# Power_Supply.net
KiCad netlist of a schematic drawn in Altium Designer
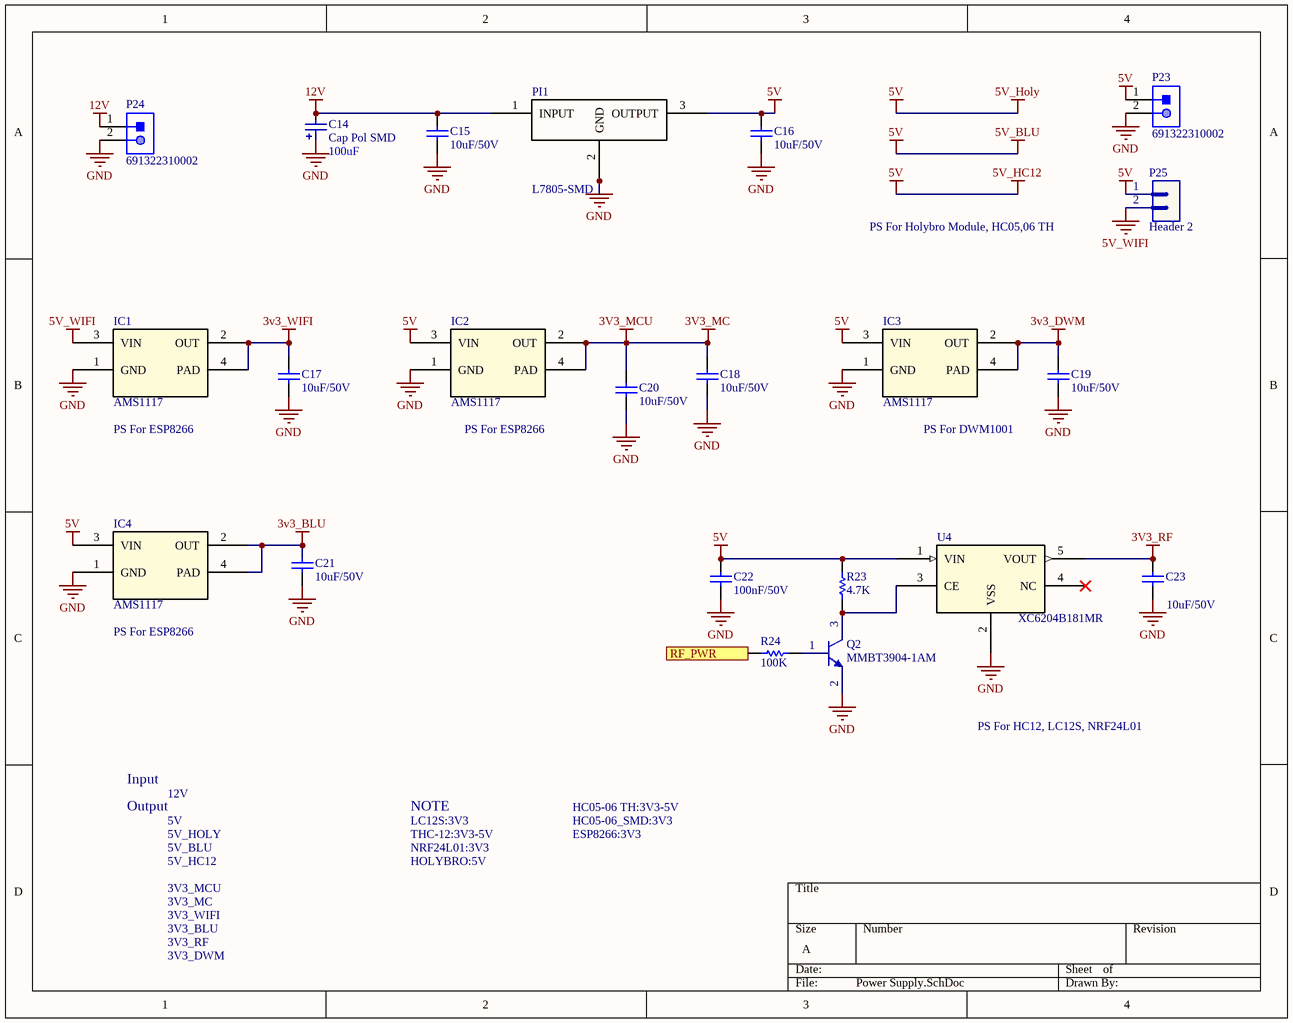
[diagram p0: Power Supply.SchDoc]

(export (version "E")
  (design (tool "Eeschema 10.0.6"))
  (components
    (comp (ref "C14")
      (value "Cap Pol SMD")
      (footprint "CAP ALU SIZE B")
      (description "Polarized Capacitor (Radial)")
      (fields (field (name "ALTIUM_VALUE") "100uF"))
      (libsource (lib "PIF_C16_lib") (part "Cap Pol SMD"))
    )
    (comp (ref "C15")
      (value "10uF/50V")
      (footprint "CAP-SM-0805")
      (description "CAP CER 10UF 50V X5R 0805")
      (fields
        (field (name "MANUFACTURER") "Yageo")
        (field (name "MANUFACTURER PART NUMBER") "CC0805KKX5R9BB106")
      )
      (libsource (lib "Capacitor") (part "Cap-10uF-50V-0805"))
    )
    (comp (ref "C16")
      (value "10uF/50V")
      (footprint "CAP-SM-0805")
      (description "CAP CER 10UF 50V X5R 0805")
      (fields
        (field (name "MANUFACTURER") "Yageo")
        (field (name "MANUFACTURER PART NUMBER") "CC0805KKX5R9BB106")
      )
      (libsource (lib "Capacitor") (part "Cap-10uF-50V-0805"))
    )
    (comp (ref "C17")
      (value "10uF/50V")
      (footprint "CAP-SM-0805")
      (description "CAP CER 10UF 50V X5R 0805")
      (fields
        (field (name "MANUFACTURER") "Yageo")
        (field (name "MANUFACTURER PART NUMBER") "CC0805KKX5R9BB106")
      )
      (libsource (lib "Capacitor") (part "Cap-10uF-50V-0805"))
    )
    (comp (ref "C18")
      (value "10uF/50V")
      (footprint "CAP-SM-0805")
      (description "CAP CER 10UF 50V X5R 0805")
      (fields
        (field (name "MANUFACTURER") "Yageo")
        (field (name "MANUFACTURER PART NUMBER") "CC0805KKX5R9BB106")
      )
      (libsource (lib "Capacitor") (part "Cap-10uF-50V-0805"))
    )
    (comp (ref "C19")
      (value "10uF/50V")
      (footprint "CAP-SM-0805")
      (description "CAP CER 10UF 50V X5R 0805")
      (fields
        (field (name "MANUFACTURER") "Yageo")
        (field (name "MANUFACTURER PART NUMBER") "CC0805KKX5R9BB106")
      )
      (libsource (lib "Capacitor") (part "Cap-10uF-50V-0805"))
    )
    (comp (ref "C20")
      (value "10uF/50V")
      (footprint "CAP-SM-0805")
      (description "CAP CER 10UF 50V X5R 0805")
      (fields
        (field (name "MANUFACTURER") "Yageo")
        (field (name "MANUFACTURER PART NUMBER") "CC0805KKX5R9BB106")
      )
      (libsource (lib "Capacitor") (part "Cap-10uF-50V-0805"))
    )
    (comp (ref "C21")
      (value "10uF/50V")
      (footprint "CAP-SM-0805")
      (description "CAP CER 10UF 50V X5R 0805")
      (fields
        (field (name "MANUFACTURER") "Yageo")
        (field (name "MANUFACTURER PART NUMBER") "CC0805KKX5R9BB106")
      )
      (libsource (lib "Capacitor") (part "Cap-10uF-50V-0805"))
    )
    (comp (ref "C22")
      (value "100nF/50V")
      (footprint "CAP-SM-0805")
      (description "CAP CER 0.1UF 50V Y5V 0805")
      (fields
        (field (name "MANUFACTURER") "Samsung Electro-Mechanics")
        (field (name "MANUFACTURER PART NUMBER") "CL21F104ZBCNNNC")
      )
      (libsource (lib "Capacitor") (part "Cap-100nF-50V-0805"))
    )
    (comp (ref "C23")
      (value "10uF/50V")
      (footprint "CAP-SM-0805")
      (description "CAP CER 10UF 50V X5R 0805")
      (fields
        (field (name "MANUFACTURER") "Yageo")
        (field (name "MANUFACTURER PART NUMBER") "CC0805KKX5R9BB106")
      )
      (libsource (lib "Capacitor") (part "Cap-10uF-50V-0805"))
    )
    (comp (ref "IC1")
      (value "AMS1117")
      (footprint "AMS1117")
      (fields (field (name "COPYRIGHT") "Copyright (C) 2018 Accelerated Designs. All rights reserved"))
      (libsource (lib "Integrated_Library") (part "AMS1117"))
    )
    (comp (ref "IC2")
      (value "AMS1117")
      (footprint "AMS1117")
      (fields (field (name "COPYRIGHT") "Copyright (C) 2018 Accelerated Designs. All rights reserved"))
      (libsource (lib "Integrated_Library") (part "AMS1117"))
    )
    (comp (ref "IC3")
      (value "AMS1117")
      (footprint "AMS1117")
      (fields (field (name "COPYRIGHT") "Copyright (C) 2018 Accelerated Designs. All rights reserved"))
      (libsource (lib "Integrated_Library") (part "AMS1117"))
    )
    (comp (ref "IC4")
      (value "AMS1117")
      (footprint "AMS1117")
      (fields (field (name "COPYRIGHT") "Copyright (C) 2018 Accelerated Designs. All rights reserved"))
      (libsource (lib "Integrated_Library") (part "AMS1117"))
    )
    (comp (ref "P23")
      (value "691322310002")
      (footprint "691322310002")
      (description "WR-TBL Serie 322 Horizontal PCB Header, Pluggable, pitch 3.81mm, 2p")
      (fields (field (name "PUBLISHER") "Wurth Elektronik"))
      (libsource (lib "691101710002_Altium_WR-TBL_rev19a") (part "691322310002"))
    )
    (comp (ref "P24")
      (value "691322310002")
      (footprint "691322310002")
      (description "WR-TBL Serie 322 Horizontal PCB Header, Pluggable, pitch 3.81mm, 2p")
      (fields (field (name "PUBLISHER") "Wurth Elektronik"))
      (libsource (lib "691101710002_Altium_WR-TBL_rev19a") (part "691322310002"))
    )
    (comp (ref "P25")
      (value "Header 2")
      (footprint "JP2")
      (description "Header, 2-Pin")
      (fields (field (name "PUBLISHER") "Altium Limited"))
      (libsource (lib "PIF_C16_lib") (part "Header 2"))
    )
    (comp (ref "PI1")
      (value "L7805-SMD")
      (footprint "D2PAk")
      (fields
        (field (name "MANUFACTURER_PART_NUMBER") "L7805CD2T-TR")
        (field (name "COPYRIGHT") "Copyright (C) 2018 Accelerated Designs. All rights reserved")
      )
      (libsource (lib "Integrated_Library") (part "L7805-SMD_1"))
    )
    (comp (ref "Q2")
      (value "MMBT3904-1AM")
      (footprint "SOT23_NEX")
      (libsource (lib "BJT") (part "MMBT3904-1AM"))
    )
    (comp (ref "R23")
      (value "4.7K")
      (footprint "Resistor:RES-SM-0805")
      (description "RES 1K OHM 1% 1/4W 0805")
      (fields
        (field (name "MANUFACTURER") "Stackpole Electronics Inc")
        (field (name "MANUFACTURER PART NUMBER") "RNCP0805FTD1K00")
      )
      (libsource (lib "Resistor") (part "Res-1K-0805"))
    )
    (comp (ref "R24")
      (value "100K")
      (footprint "Resistor:RES-SM-0805")
      (description "RES 1K OHM 1% 1/4W 0805")
      (fields
        (field (name "MANUFACTURER") "Stackpole Electronics Inc")
        (field (name "MANUFACTURER PART NUMBER") "RNCP0805FTD1K00")
      )
      (libsource (lib "Resistor") (part "Res-1K-0805"))
    )
    (comp (ref "U4")
      (value "XC6204B181MR")
      (footprint "XC6204B332MR")
      (fields (field (name "COPYRIGHT") "Copyright (C) 2018 Accelerated Designs. All rights reserved"))
      (libsource (lib "Integrated_Library") (part "XC6204B181MR"))
    )
  )
  (nets
    (net (code "1") (name "/RF_PWR") (class "Default")
      (node (ref "R24") (pin "2") (pinfunction "2_2") (pintype "passive"))
    )
    (net (code "2") (name "3V3_MC") (class "Default")
      (node (ref "C18") (pin "2") (pinfunction "2_2") (pintype "passive"))
      (node (ref "C20") (pin "2") (pinfunction "2_2") (pintype "passive"))
      (node (ref "IC2") (pin "2") (pinfunction "OUT_2") (pintype "open_collector"))
      (node (ref "IC2") (pin "4") (pinfunction "PAD_4") (pintype "power_in"))
    )
    (net (code "3") (name "3V3_RF") (class "Default")
      (node (ref "C23") (pin "2") (pinfunction "2_2") (pintype "passive"))
      (node (ref "U4") (pin "5") (pinfunction "VOUT_5") (pintype "output"))
    )
    (net (code "4") (name "3v3_BLU") (class "Default")
      (node (ref "C21") (pin "2") (pinfunction "2_2") (pintype "passive"))
      (node (ref "IC4") (pin "2") (pinfunction "OUT_2") (pintype "open_collector"))
      (node (ref "IC4") (pin "4") (pinfunction "PAD_4") (pintype "power_in"))
    )
    (net (code "5") (name "3v3_DWM") (class "Default")
      (node (ref "C19") (pin "2") (pinfunction "2_2") (pintype "passive"))
      (node (ref "IC3") (pin "2") (pinfunction "OUT_2") (pintype "open_collector"))
      (node (ref "IC3") (pin "4") (pinfunction "PAD_4") (pintype "power_in"))
    )
    (net (code "6") (name "3v3_WIFI") (class "Default")
      (node (ref "C17") (pin "2") (pinfunction "2_2") (pintype "passive"))
      (node (ref "IC1") (pin "2") (pinfunction "OUT_2") (pintype "open_collector"))
      (node (ref "IC1") (pin "4") (pinfunction "PAD_4") (pintype "power_in"))
    )
    (net (code "7") (name "5V") (class "Default")
      (node (ref "C16") (pin "2") (pinfunction "2_2") (pintype "passive"))
      (node (ref "C22") (pin "2") (pinfunction "2_2") (pintype "passive"))
      (node (ref "IC2") (pin "3") (pinfunction "VIN_3") (pintype "open_collector"))
      (node (ref "IC3") (pin "3") (pinfunction "VIN_3") (pintype "open_collector"))
      (node (ref "IC4") (pin "3") (pinfunction "VIN_3") (pintype "open_collector"))
      (node (ref "P23") (pin "1") (pinfunction "1_1") (pintype "passive"))
      (node (ref "P25") (pin "1") (pinfunction "1_1") (pintype "passive"))
      (node (ref "PI1") (pin "3") (pinfunction "OUTPUT_3") (pintype "passive"))
      (node (ref "R23") (pin "2") (pinfunction "2_2") (pintype "passive"))
      (node (ref "U4") (pin "1") (pinfunction "VIN_1") (pintype "input"))
    )
    (net (code "8") (name "5V_WIFI") (class "Default")
      (node (ref "IC1") (pin "3") (pinfunction "VIN_3") (pintype "open_collector"))
      (node (ref "P25") (pin "2") (pinfunction "2_2") (pintype "passive"))
    )
    (net (code "9") (name "12V") (class "Default")
      (node (ref "C14") (pin "2") (pinfunction "2_2") (pintype "passive"))
      (node (ref "C15") (pin "2") (pinfunction "2_2") (pintype "passive"))
      (node (ref "P24") (pin "1") (pinfunction "1_1") (pintype "passive"))
      (node (ref "PI1") (pin "1") (pinfunction "INPUT_1") (pintype "passive"))
    )
    (net (code "10") (name "GND") (class "Default")
      (node (ref "C14") (pin "1") (pinfunction "1_1") (pintype "passive"))
      (node (ref "C15") (pin "1") (pinfunction "1_1") (pintype "passive"))
      (node (ref "C16") (pin "1") (pinfunction "1_1") (pintype "passive"))
      (node (ref "C17") (pin "1") (pinfunction "1_1") (pintype "passive"))
      (node (ref "C18") (pin "1") (pinfunction "1_1") (pintype "passive"))
      (node (ref "C19") (pin "1") (pinfunction "1_1") (pintype "passive"))
      (node (ref "C20") (pin "1") (pinfunction "1_1") (pintype "passive"))
      (node (ref "C21") (pin "1") (pinfunction "1_1") (pintype "passive"))
      (node (ref "C22") (pin "1") (pinfunction "1_1") (pintype "passive"))
      (node (ref "C23") (pin "1") (pinfunction "1_1") (pintype "passive"))
      (node (ref "IC1") (pin "1") (pinfunction "GND_1") (pintype "passive"))
      (node (ref "IC2") (pin "1") (pinfunction "GND_1") (pintype "passive"))
      (node (ref "IC3") (pin "1") (pinfunction "GND_1") (pintype "passive"))
      (node (ref "IC4") (pin "1") (pinfunction "GND_1") (pintype "passive"))
      (node (ref "P23") (pin "2") (pinfunction "2_2") (pintype "passive"))
      (node (ref "P24") (pin "2") (pinfunction "2_2") (pintype "passive"))
      (node (ref "PI1") (pin "2") (pinfunction "GND_2") (pintype "passive"))
      (node (ref "Q2") (pin "2") (pinfunction "E_2") (pintype "passive"))
      (node (ref "U4") (pin "2") (pinfunction "VSS_2") (pintype "passive"))
    )
    (net (code "11") (name "Net-(Q2-B)") (class "Default")
      (node (ref "Q2") (pin "1") (pinfunction "B_1") (pintype "passive"))
      (node (ref "R24") (pin "1") (pinfunction "1_1") (pintype "passive"))
    )
    (net (code "12") (name "Net-(Q2-C)") (class "Default")
      (node (ref "Q2") (pin "3") (pinfunction "C_3") (pintype "passive"))
      (node (ref "R23") (pin "1") (pinfunction "1_1") (pintype "passive"))
      (node (ref "U4") (pin "3") (pinfunction "CE_3") (pintype "passive"))
    )
    (net (code "13") (name "unconnected-(U4-NC-Pad4)") (class "Default")
      (node (ref "U4") (pin "4") (pinfunction "NC_4") (pintype "open_collector+no_connect"))
    )
  )
)
